# Snap21.net
KiCad netlist of a schematic drawn in Altium Designer
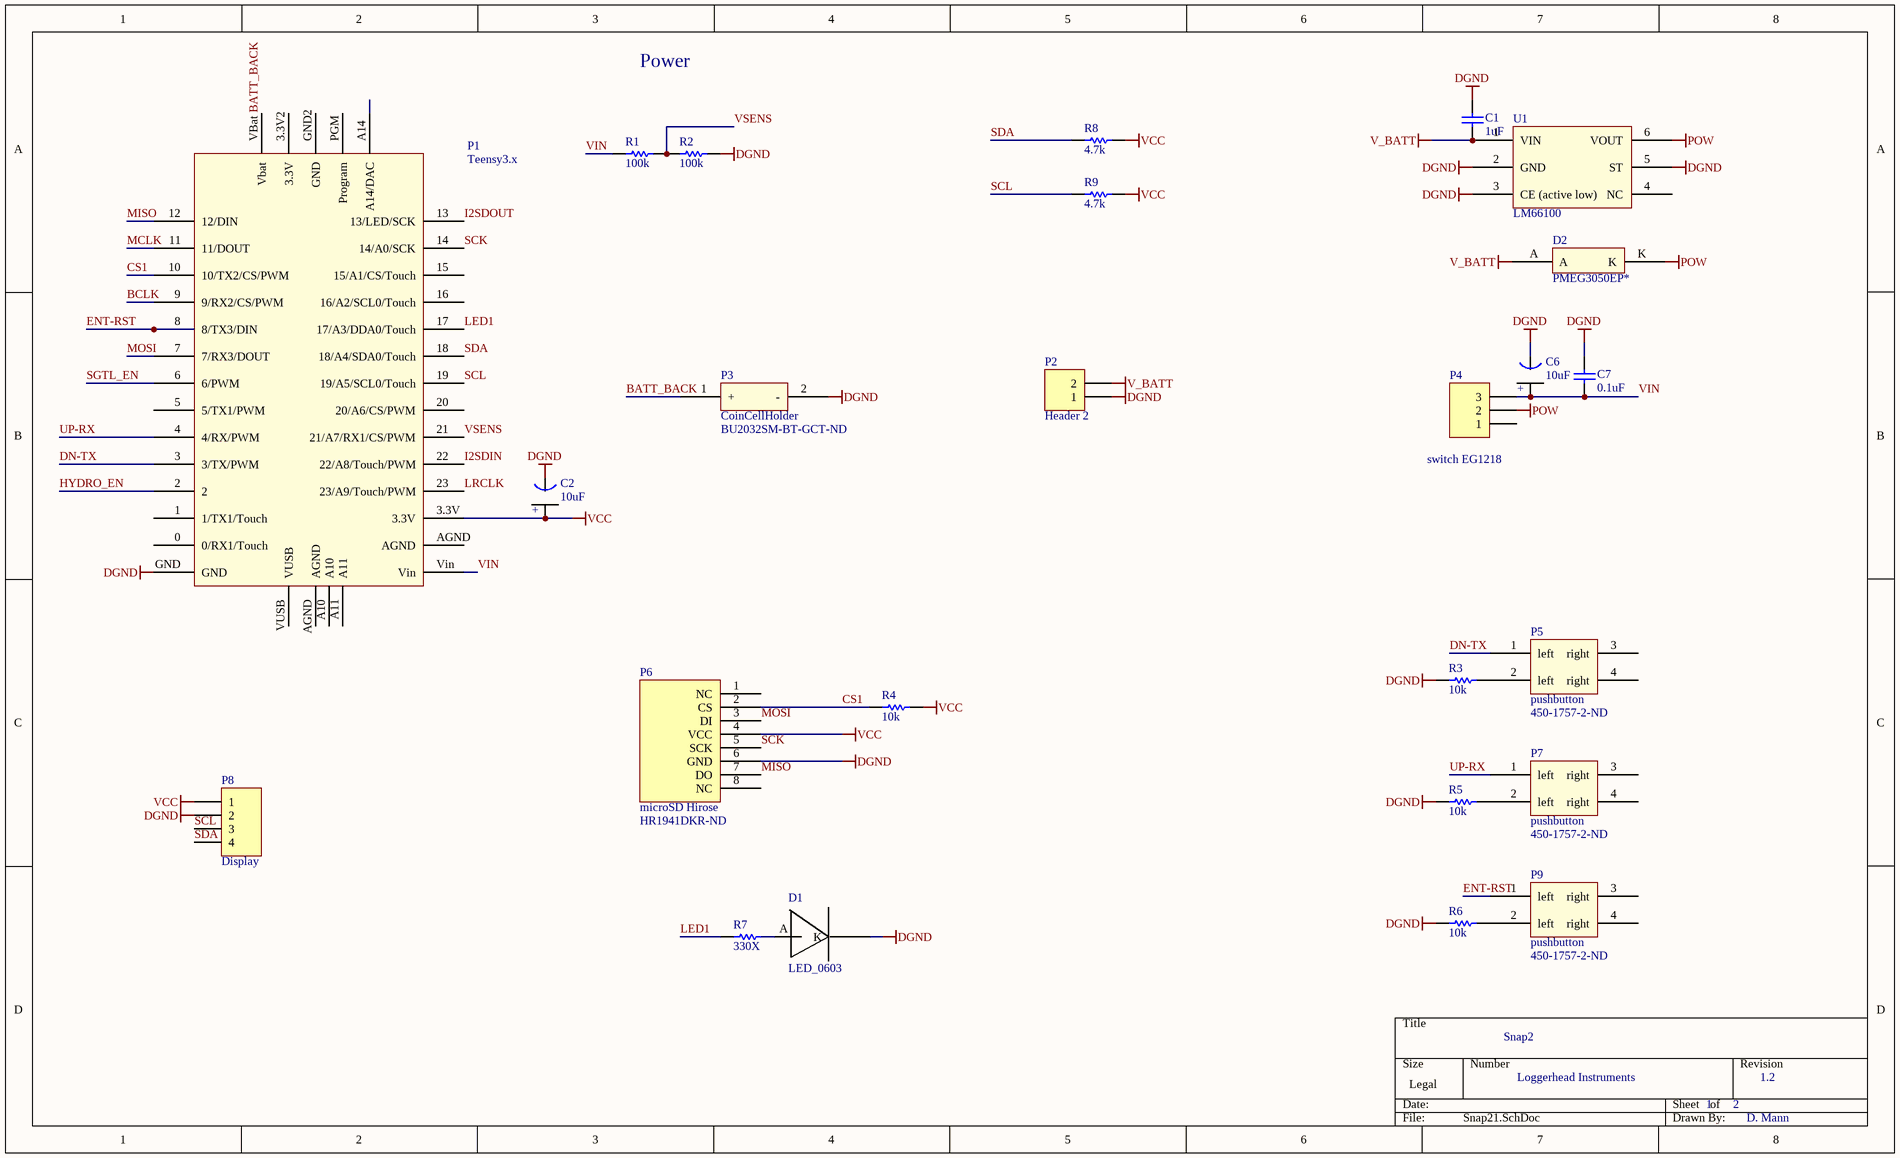
[diagram p0: Snap21.SchDoc]

(export (version "E")
  (design (tool "Eeschema 10.0.6"))
  (components
    (comp (ref "C1")
      (value "1uF")
      (footprint "0402")
      (description "Ceramic Chip Capacitor - Standard")
      (fields (field (name "PUBLISHER") "Altium Limited"))
      (libsource (lib "KEMET Chip Capacitor") (part "C0402"))
    )
    (comp (ref "C2") (value "10uF") (footprint "Tant0805") (libsource (lib "Loggerhead") (part "Tant0805")))
    (comp (ref "C6") (value "10uF") (footprint "Tant0805") (libsource (lib "Loggerhead") (part "Tant0805")))
    (comp (ref "C7")
      (value "0.1uF")
      (footprint "0402")
      (description "Ceramic Chip Capacitor - Standard")
      (fields (field (name "PUBLISHER") "Altium Limited"))
      (libsource (lib "KEMET Chip Capacitor") (part "C0402"))
    )
    (comp (ref "D1")
      (value "LED_0603")
      (footprint "Diode0603")
      (libsource (lib "Loggerhead") (part "LED_0603"))
    )
    (comp (ref "D2")
      (value "PMEG3050EP*")
      (footprint "Diode_PMEG3050EP")
      (libsource (lib "Loggerhead") (part "Diode_PMEG3050EP"))
    )
    (comp (ref "P1")
      (value "Teensy3.x")
      (footprint "Teensy3.x")
      (libsource (lib "Teensy") (part "Teensy3.x"))
    )
    (comp (ref "P2")
      (value "Header 2")
      (footprint "HDR1X2")
      (description "Header, 2-Pin")
      (fields (field (name "PUBLISHER") "Altium Limited"))
      (libsource (lib "Miscellaneous Connectors") (part "Header 2"))
    )
    (comp (ref "P3")
      (value "CoinCellHolder")
      (footprint "CoinCellHolder")
      (fields (field (name "SUPPLIER PART NUMBER 1") "BU2032SM-BT-GCT-ND"))
      (libsource (lib "Loggerhead") (part "CoinCellHolder"))
    )
    (comp (ref "P4")
      (value "switch EG1218")
      (footprint "HDR1X3")
      (description "Header, 3-Pin")
      (fields (field (name "PUBLISHER") "Altium Limited"))
      (libsource (lib "Miscellaneous Connectors") (part "Header 3"))
    )
    (comp (ref "P5")
      (value "pushbutton")
      (footprint "SOP4")
      (fields (field (name "SUPPLIER PART NUMBER 1") "450-1757-2-ND"))
      (libsource (lib "Loggerhead") (part "pushbutton"))
    )
    (comp (ref "P6")
      (value "microSD Hirose")
      (footprint "DM3D microSD")
      (fields (field (name "SUPPLIER PART NUMBER 1") "HR1941DKR-ND"))
      (libsource (lib "Loggerhead") (part "microSD Hirose"))
    )
    (comp (ref "P7")
      (value "pushbutton")
      (footprint "SOP4")
      (fields (field (name "SUPPLIER PART NUMBER 1") "450-1757-2-ND"))
      (libsource (lib "Loggerhead") (part "pushbutton"))
    )
    (comp (ref "P8")
      (value "Display")
      (footprint "HDR1X4")
      (description "Header, 4-Pin")
      (fields (field (name "PUBLISHER") "Altium Limited"))
      (libsource (lib "Miscellaneous Connectors") (part "Header 4"))
    )
    (comp (ref "P9")
      (value "pushbutton")
      (footprint "SOP4")
      (fields (field (name "SUPPLIER PART NUMBER 1") "450-1757-2-ND"))
      (libsource (lib "Loggerhead") (part "pushbutton"))
    )
    (comp (ref "R1")
      (value "100k")
      (footprint "3-0603")
      (fields (field (name "PUBLISHER") "Altium Limited"))
      (libsource (lib "Panasonic Resistor") (part "ERJ3RK"))
    )
    (comp (ref "R2")
      (value "100k")
      (footprint "3-0603")
      (fields (field (name "PUBLISHER") "Altium Limited"))
      (libsource (lib "Panasonic Resistor") (part "ERJ3RK"))
    )
    (comp (ref "R3")
      (value "10k")
      (footprint "3-0603")
      (fields (field (name "PUBLISHER") "Altium Limited"))
      (libsource (lib "Panasonic Resistor") (part "ERJ3RK"))
    )
    (comp (ref "R4")
      (value "10k")
      (footprint "3-0603")
      (fields (field (name "PUBLISHER") "Altium Limited"))
      (libsource (lib "Panasonic Resistor") (part "ERJ3RK"))
    )
    (comp (ref "R5")
      (value "10k")
      (footprint "3-0603")
      (fields (field (name "PUBLISHER") "Altium Limited"))
      (libsource (lib "Panasonic Resistor") (part "ERJ3RK"))
    )
    (comp (ref "R6")
      (value "10k")
      (footprint "3-0603")
      (fields (field (name "PUBLISHER") "Altium Limited"))
      (libsource (lib "Panasonic Resistor") (part "ERJ3RK"))
    )
    (comp (ref "R7")
      (value "330X")
      (footprint "3-0603")
      (fields (field (name "PUBLISHER") "Altium Limited"))
      (libsource (lib "Panasonic Resistor") (part "ERJ3RK"))
    )
    (comp (ref "R8")
      (value "4.7k")
      (footprint "3-0603")
      (fields (field (name "PUBLISHER") "Altium Limited"))
      (libsource (lib "Panasonic Resistor") (part "ERJ3RK"))
    )
    (comp (ref "R9")
      (value "4.7k")
      (footprint "3-0603")
      (fields (field (name "PUBLISHER") "Altium Limited"))
      (libsource (lib "Panasonic Resistor") (part "ERJ3RK"))
    )
    (comp (ref "U1") (value "LM66100") (footprint "SC-70-6") (libsource (lib "Loggerhead") (part "LM66100")))
  )
  (nets
    (net (code "1") (name "/BATT_BACK") (class "Default")
      (node (ref "P1") (pin "VBat") (pinfunction "Vbat_VBat") (pintype "passive"))
      (node (ref "P3") (pin "1") (pinfunction "+_1") (pintype "passive"))
    )
    (net (code "2") (name "/BCLK") (class "Default")
      (node (ref "P1") (pin "9") (pinfunction "9/RX2/CS/PWM_9") (pintype "passive"))
    )
    (net (code "3") (name "/CS1") (class "Default")
      (node (ref "P1") (pin "10") (pinfunction "10/TX2/CS/PWM_10") (pintype "passive"))
      (node (ref "P6") (pin "2") (pinfunction "CS_2") (pintype "passive"))
      (node (ref "R4") (pin "2") (pinfunction "2_2") (pintype "passive"))
    )
    (net (code "4") (name "/DN-TX") (class "Default")
      (node (ref "P1") (pin "3") (pinfunction "3/TX/PWM_3") (pintype "passive"))
      (node (ref "P5") (pin "1") (pinfunction "left_1") (pintype "passive"))
    )
    (net (code "5") (name "/ENT-RST") (class "Default")
      (node (ref "P1") (pin "8") (pinfunction "8/TX3/DIN_8") (pintype "passive"))
      (node (ref "P9") (pin "1") (pinfunction "left_1") (pintype "passive"))
    )
    (net (code "6") (name "/HYDRO_EN") (class "Default")
      (node (ref "P1") (pin "2") (pinfunction "2_2") (pintype "passive"))
    )
    (net (code "7") (name "/I2SDIN") (class "Default")
      (node (ref "P1") (pin "22") (pinfunction "22/A8/Touch/PWM_22") (pintype "passive"))
    )
    (net (code "8") (name "/I2SDOUT") (class "Default")
      (node (ref "P1") (pin "13") (pinfunction "13/LED/SCK_13") (pintype "passive"))
    )
    (net (code "9") (name "/LED1") (class "Default")
      (node (ref "P1") (pin "17") (pinfunction "17/A3/DDA0/Touch_17") (pintype "passive"))
      (node (ref "R7") (pin "1") (pinfunction "1_1") (pintype "passive"))
    )
    (net (code "10") (name "/LRCLK") (class "Default")
      (node (ref "P1") (pin "23") (pinfunction "23/A9/Touch/PWM_23") (pintype "passive"))
    )
    (net (code "11") (name "/MCLK") (class "Default")
      (node (ref "P1") (pin "11") (pinfunction "11/DOUT_11") (pintype "passive"))
    )
    (net (code "12") (name "/MISO") (class "Default")
      (node (ref "P1") (pin "12") (pinfunction "12/DIN_12") (pintype "passive"))
      (node (ref "P6") (pin "7") (pinfunction "DO_7") (pintype "passive"))
    )
    (net (code "13") (name "/MOSI") (class "Default")
      (node (ref "P1") (pin "7") (pinfunction "7/RX3/DOUT_7") (pintype "passive"))
      (node (ref "P6") (pin "3") (pinfunction "DI_3") (pintype "passive"))
    )
    (net (code "14") (name "/SCK") (class "Default")
      (node (ref "P1") (pin "14") (pinfunction "14/A0/SCK_14") (pintype "passive"))
      (node (ref "P6") (pin "5") (pinfunction "SCK_5") (pintype "passive"))
    )
    (net (code "15") (name "/SCL") (class "Default")
      (node (ref "P1") (pin "19") (pinfunction "19/A5/SCL0/Touch_19") (pintype "passive"))
      (node (ref "P8") (pin "3") (pinfunction "3_3") (pintype "passive"))
      (node (ref "R9") (pin "1") (pinfunction "1_1") (pintype "passive"))
    )
    (net (code "16") (name "/SDA") (class "Default")
      (node (ref "P1") (pin "18") (pinfunction "18/A4/SDA0/Touch_18") (pintype "passive"))
      (node (ref "P8") (pin "4") (pinfunction "4_4") (pintype "passive"))
      (node (ref "R8") (pin "1") (pinfunction "1_1") (pintype "passive"))
    )
    (net (code "17") (name "/SGTL_EN") (class "Default")
      (node (ref "P1") (pin "6") (pinfunction "6/PWM_6") (pintype "passive"))
    )
    (net (code "18") (name "/UP-RX") (class "Default")
      (node (ref "P1") (pin "4") (pinfunction "4/RX/PWM_4") (pintype "passive"))
      (node (ref "P7") (pin "1") (pinfunction "left_1") (pintype "passive"))
    )
    (net (code "19") (name "/VIN") (class "Default")
      (node (ref "C6") (pin "2") (pinfunction "+_2") (pintype "passive"))
      (node (ref "C7") (pin "1") (pinfunction "1_1") (pintype "passive"))
      (node (ref "P1") (pin "Vin") (pinfunction "Vin_Vin") (pintype "passive"))
      (node (ref "P4") (pin "3") (pinfunction "3_3") (pintype "passive"))
      (node (ref "R1") (pin "2") (pinfunction "2_2") (pintype "passive"))
    )
    (net (code "20") (name "/VSENS") (class "Default")
      (node (ref "P1") (pin "21") (pinfunction "21/A7/RX1/CS/PWM_21") (pintype "passive"))
      (node (ref "R1") (pin "1") (pinfunction "1_1") (pintype "passive"))
      (node (ref "R2") (pin "2") (pinfunction "2_2") (pintype "passive"))
    )
    (net (code "21") (name "DGND") (class "Default")
      (node (ref "C1") (pin "1") (pinfunction "1_1") (pintype "passive"))
      (node (ref "C2") (pin "1") (pinfunction "GND_1") (pintype "passive"))
      (node (ref "C6") (pin "1") (pinfunction "GND_1") (pintype "passive"))
      (node (ref "C7") (pin "2") (pinfunction "2_2") (pintype "passive"))
      (node (ref "D1") (pin "K") (pinfunction "K_K") (pintype "passive"))
      (node (ref "P1") (pin "GND") (pinfunction "GND_GND") (pintype "passive"))
      (node (ref "P2") (pin "1") (pinfunction "1_1") (pintype "passive"))
      (node (ref "P3") (pin "2") (pinfunction "-_2") (pintype "passive"))
      (node (ref "P6") (pin "6") (pinfunction "GND_6") (pintype "passive"))
      (node (ref "P8") (pin "2") (pinfunction "2_2") (pintype "passive"))
      (node (ref "R2") (pin "1") (pinfunction "1_1") (pintype "passive"))
      (node (ref "R3") (pin "2") (pinfunction "2_2") (pintype "passive"))
      (node (ref "R5") (pin "2") (pinfunction "2_2") (pintype "passive"))
      (node (ref "R6") (pin "2") (pinfunction "2_2") (pintype "passive"))
      (node (ref "U1") (pin "2") (pinfunction "GND_2") (pintype "passive"))
      (node (ref "U1") (pin "3") (pinfunction "CE_(active_low)_3") (pintype "passive"))
      (node (ref "U1") (pin "5") (pinfunction "ST_5") (pintype "passive"))
    )
    (net (code "22") (name "Net-(D1-PadA)") (class "Default")
      (node (ref "D1") (pin "A") (pinfunction "A_A") (pintype "passive"))
      (node (ref "R7") (pin "2") (pinfunction "2_2") (pintype "passive"))
    )
    (net (code "23") (name "Net-(P5-left-Pad2)") (class "Default")
      (node (ref "P5") (pin "2") (pinfunction "left_2") (pintype "passive"))
      (node (ref "R3") (pin "1") (pinfunction "1_1") (pintype "passive"))
    )
    (net (code "24") (name "Net-(P7-left-Pad2)") (class "Default")
      (node (ref "P7") (pin "2") (pinfunction "left_2") (pintype "passive"))
      (node (ref "R5") (pin "1") (pinfunction "1_1") (pintype "passive"))
    )
    (net (code "25") (name "Net-(P9-left-Pad2)") (class "Default")
      (node (ref "P9") (pin "2") (pinfunction "left_2") (pintype "passive"))
      (node (ref "R6") (pin "1") (pinfunction "1_1") (pintype "passive"))
    )
    (net (code "26") (name "POW") (class "Default")
      (node (ref "D2") (pin "K") (pinfunction "K_K") (pintype "passive"))
      (node (ref "P4") (pin "2") (pinfunction "2_2") (pintype "passive"))
      (node (ref "U1") (pin "6") (pinfunction "VOUT_6") (pintype "passive"))
    )
    (net (code "27") (name "VCC") (class "Default")
      (node (ref "C2") (pin "2") (pinfunction "+_2") (pintype "passive"))
      (node (ref "P1") (pin "3.3V") (pinfunction "3.3V_3.3V") (pintype "passive"))
      (node (ref "P6") (pin "4") (pinfunction "VCC_4") (pintype "passive"))
      (node (ref "P8") (pin "1") (pinfunction "1_1") (pintype "passive"))
      (node (ref "R4") (pin "1") (pinfunction "1_1") (pintype "passive"))
      (node (ref "R8") (pin "2") (pinfunction "2_2") (pintype "passive"))
      (node (ref "R9") (pin "2") (pinfunction "2_2") (pintype "passive"))
    )
    (net (code "28") (name "V_BATT") (class "Default")
      (node (ref "C1") (pin "2") (pinfunction "2_2") (pintype "passive"))
      (node (ref "D2") (pin "A") (pinfunction "A_A") (pintype "passive"))
      (node (ref "P2") (pin "2") (pinfunction "2_2") (pintype "passive"))
      (node (ref "U1") (pin "1") (pinfunction "VIN_1") (pintype "passive"))
    )
    (net (code "29") (name "unconnected-(P1-0{slash}RX1{slash}Touch-Pad0)") (class "Default")
      (node (ref "P1") (pin "0") (pinfunction "0/RX1/Touch_0") (pintype "passive"))
    )
    (net (code "30") (name "unconnected-(P1-1{slash}TX1{slash}Touch-Pad1)") (class "Default")
      (node (ref "P1") (pin "1") (pinfunction "1/TX1/Touch_1") (pintype "passive"))
    )
    (net (code "31") (name "unconnected-(P1-3.3V-Pad3.3V2)") (class "Default")
      (node (ref "P1") (pin "3.3V2") (pinfunction "3.3V_3.3V2") (pintype "passive"))
    )
    (net (code "32") (name "unconnected-(P1-5{slash}TX1{slash}PWM-Pad5)") (class "Default")
      (node (ref "P1") (pin "5") (pinfunction "5/TX1/PWM_5") (pintype "passive"))
    )
    (net (code "33") (name "unconnected-(P1-15{slash}A1{slash}CS{slash}Touch-Pad15)") (class "Default")
      (node (ref "P1") (pin "15") (pinfunction "15/A1/CS/Touch_15") (pintype "passive"))
    )
    (net (code "34") (name "unconnected-(P1-16{slash}A2{slash}SCL0{slash}Touch-Pad16)") (class "Default")
      (node (ref "P1") (pin "16") (pinfunction "16/A2/SCL0/Touch_16") (pintype "passive"))
    )
    (net (code "35") (name "unconnected-(P1-20{slash}A6{slash}CS{slash}PWM-Pad20)") (class "Default")
      (node (ref "P1") (pin "20") (pinfunction "20/A6/CS/PWM_20") (pintype "passive"))
    )
    (net (code "36") (name "unconnected-(P1-A14{slash}DAC-PadA14)") (class "Default")
      (node (ref "P1") (pin "A14") (pinfunction "A14/DAC_A14") (pintype "passive"))
    )
    (net (code "37") (name "unconnected-(P1-GND-PadGND2)") (class "Default")
      (node (ref "P1") (pin "GND2") (pinfunction "GND_GND2") (pintype "passive"))
    )
    (net (code "38") (name "unconnected-(P1-PadA10)") (class "Default")
      (node (ref "P1") (pin "A10") (pinfunction "A10_A10") (pintype "passive"))
    )
    (net (code "39") (name "unconnected-(P1-PadA11)") (class "Default")
      (node (ref "P1") (pin "A11") (pinfunction "A11_A11") (pintype "passive"))
    )
    (net (code "40") (name "unconnected-(P1-PadAGND)") (class "Default")
      (node (ref "P1") (pin "AGND") (pinfunction "AGND_AGND") (pintype "passive"))
    )
    (net (code "41") (name "unconnected-(P1-PadAGND)_1") (class "Default")
      (node (ref "P1") (pin "AGND") (pinfunction "AGND_AGND") (pintype "passive"))
    )
    (net (code "42") (name "unconnected-(P1-PadVUSB)") (class "Default")
      (node (ref "P1") (pin "VUSB") (pinfunction "VUSB_VUSB") (pintype "passive"))
    )
    (net (code "43") (name "unconnected-(P1-Program-PadPGM)") (class "Default")
      (node (ref "P1") (pin "PGM") (pinfunction "Program_PGM") (pintype "passive"))
    )
    (net (code "44") (name "unconnected-(P4-Pad1)") (class "Default")
      (node (ref "P4") (pin "1") (pinfunction "1_1") (pintype "passive"))
    )
    (net (code "45") (name "unconnected-(P5-right-Pad3)") (class "Default")
      (node (ref "P5") (pin "3") (pinfunction "right_3") (pintype "passive"))
    )
    (net (code "46") (name "unconnected-(P5-right-Pad4)") (class "Default")
      (node (ref "P5") (pin "4") (pinfunction "right_4") (pintype "passive"))
    )
    (net (code "47") (name "unconnected-(P6-NC-Pad1)") (class "Default")
      (node (ref "P6") (pin "1") (pinfunction "NC_1") (pintype "passive"))
    )
    (net (code "48") (name "unconnected-(P6-NC-Pad8)") (class "Default")
      (node (ref "P6") (pin "8") (pinfunction "NC_8") (pintype "passive"))
    )
    (net (code "49") (name "unconnected-(P7-right-Pad3)") (class "Default")
      (node (ref "P7") (pin "3") (pinfunction "right_3") (pintype "passive"))
    )
    (net (code "50") (name "unconnected-(P7-right-Pad4)") (class "Default")
      (node (ref "P7") (pin "4") (pinfunction "right_4") (pintype "passive"))
    )
    (net (code "51") (name "unconnected-(P9-right-Pad3)") (class "Default")
      (node (ref "P9") (pin "3") (pinfunction "right_3") (pintype "passive"))
    )
    (net (code "52") (name "unconnected-(P9-right-Pad4)") (class "Default")
      (node (ref "P9") (pin "4") (pinfunction "right_4") (pintype "passive"))
    )
    (net (code "53") (name "unconnected-(U1-NC-Pad4)") (class "Default")
      (node (ref "U1") (pin "4") (pinfunction "NC_4") (pintype "passive"))
    )
  )
)
